# Cooler.net
KiCad netlist of a schematic drawn in EAGLE
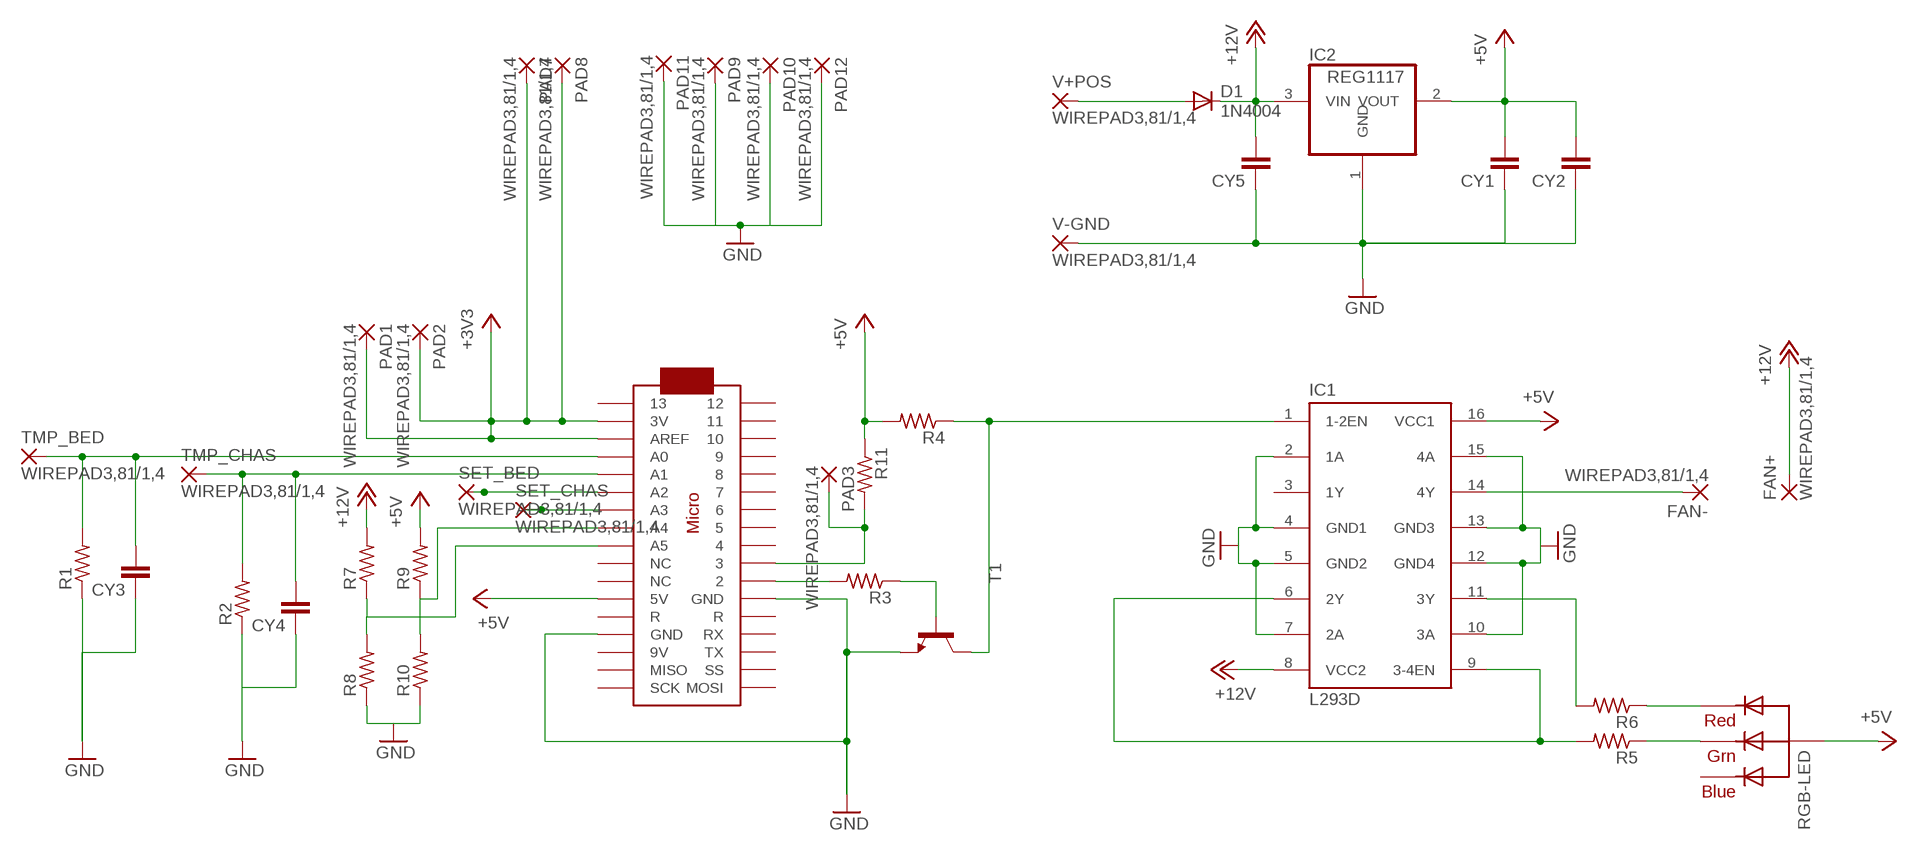
[diagram p0: schematic, sheet 1]

(export (version "E")
  (design (tool "Eeschema 10.0.6"))
  (components
    (comp (ref "CY1")
      (value "CYYC7B5")
      (footprint "eagle-import:YC7B5")
      (libsource (lib "eagle-import") (part "CYYC7B5"))
    )
    (comp (ref "CY2")
      (value "CYYC7B5")
      (footprint "eagle-import:YC7B5")
      (libsource (lib "eagle-import") (part "CYYC7B5"))
    )
    (comp (ref "CY3")
      (value "CYYC7B5")
      (footprint "eagle-import:YC7B5")
      (libsource (lib "eagle-import") (part "CYYC7B5"))
    )
    (comp (ref "CY4")
      (value "CYYC7B5")
      (footprint "eagle-import:YC7B5")
      (libsource (lib "eagle-import") (part "CYYC7B5"))
    )
    (comp (ref "CY5")
      (value "CYYC7B5")
      (footprint "eagle-import:YC7B5")
      (libsource (lib "eagle-import") (part "CYYC7B5"))
    )
    (comp (ref "D1")
      (value "1N4004")
      (footprint "eagle-import:DO41-10")
      (libsource (lib "eagle-import") (part "1N4004"))
    )
    (comp (ref "FAN+")
      (value "WIREPAD3,81/1,4")
      (footprint "eagle-import:3,81_1,4")
      (libsource (lib "eagle-import") (part "WIREPAD3,81/1,4"))
    )
    (comp (ref "FAN-")
      (value "WIREPAD3,81/1,4")
      (footprint "eagle-import:3,81_1,4")
      (libsource (lib "eagle-import") (part "WIREPAD3,81/1,4"))
    )
    (comp (ref "IC1")
      (value "L293D")
      (footprint "eagle-import:DIL16")
      (libsource (lib "eagle-import") (part "L293D"))
    )
    (comp (ref "IC2")
      (value "REG1117")
      (footprint "eagle-import:SOT223")
      (libsource (lib "eagle-import") (part "REG1117"))
    )
    (comp (ref "PAD1")
      (value "WIREPAD3,81/1,4")
      (footprint "eagle-import:3,81_1,4")
      (libsource (lib "eagle-import") (part "WIREPAD3,81/1,4"))
    )
    (comp (ref "PAD2")
      (value "WIREPAD3,81/1,4")
      (footprint "eagle-import:3,81_1,4")
      (libsource (lib "eagle-import") (part "WIREPAD3,81/1,4"))
    )
    (comp (ref "PAD3")
      (value "WIREPAD3,81/1,4")
      (footprint "eagle-import:3,81_1,4")
      (libsource (lib "eagle-import") (part "WIREPAD3,81/1,4"))
    )
    (comp (ref "PAD7")
      (value "WIREPAD3,81/1,4")
      (footprint "eagle-import:3,81_1,4")
      (libsource (lib "eagle-import") (part "WIREPAD3,81/1,4"))
    )
    (comp (ref "PAD8")
      (value "WIREPAD3,81/1,4")
      (footprint "eagle-import:3,81_1,4")
      (libsource (lib "eagle-import") (part "WIREPAD3,81/1,4"))
    )
    (comp (ref "PAD9")
      (value "WIREPAD3,81/1,4")
      (footprint "eagle-import:3,81_1,4")
      (libsource (lib "eagle-import") (part "WIREPAD3,81/1,4"))
    )
    (comp (ref "PAD10")
      (value "WIREPAD3,81/1,4")
      (footprint "eagle-import:3,81_1,4")
      (libsource (lib "eagle-import") (part "WIREPAD3,81/1,4"))
    )
    (comp (ref "PAD11")
      (value "WIREPAD3,81/1,4")
      (footprint "eagle-import:3,81_1,4")
      (libsource (lib "eagle-import") (part "WIREPAD3,81/1,4"))
    )
    (comp (ref "PAD12")
      (value "WIREPAD3,81/1,4")
      (footprint "eagle-import:3,81_1,4")
      (libsource (lib "eagle-import") (part "WIREPAD3,81/1,4"))
    )
    (comp (ref "R1")
      (value "R-US_0309/10")
      (footprint "eagle-import:0309_10")
      (libsource (lib "eagle-import") (part "R-US_0309/10"))
    )
    (comp (ref "R2")
      (value "R-US_0309/10")
      (footprint "eagle-import:0309_10")
      (libsource (lib "eagle-import") (part "R-US_0309/10"))
    )
    (comp (ref "R3")
      (value "R-US_0309/10")
      (footprint "eagle-import:0309_10")
      (libsource (lib "eagle-import") (part "R-US_0309/10"))
    )
    (comp (ref "R4")
      (value "R-US_0309/10")
      (footprint "eagle-import:0309_10")
      (libsource (lib "eagle-import") (part "R-US_0309/10"))
    )
    (comp (ref "R5")
      (value "R-US_0309/12")
      (footprint "eagle-import:0309_12")
      (libsource (lib "eagle-import") (part "R-US_0309/12"))
    )
    (comp (ref "R6")
      (value "R-US_0309/12")
      (footprint "eagle-import:0309_12")
      (libsource (lib "eagle-import") (part "R-US_0309/12"))
    )
    (comp (ref "R7")
      (value "R-US_0309/12")
      (footprint "eagle-import:0309_12")
      (libsource (lib "eagle-import") (part "R-US_0309/12"))
    )
    (comp (ref "R8")
      (value "R-US_0309/10")
      (footprint "eagle-import:0309_10")
      (libsource (lib "eagle-import") (part "R-US_0309/10"))
    )
    (comp (ref "R9")
      (value "R-US_0309/12")
      (footprint "eagle-import:0309_12")
      (libsource (lib "eagle-import") (part "R-US_0309/12"))
    )
    (comp (ref "R10")
      (value "R-US_0309/10")
      (footprint "eagle-import:0309_10")
      (libsource (lib "eagle-import") (part "R-US_0309/10"))
    )
    (comp (ref "R11")
      (value "R-US_0309/10")
      (footprint "eagle-import:0309_10")
      (libsource (lib "eagle-import") (part "R-US_0309/10"))
    )
    (comp (ref "RGB-LED")
      (value "RGBLED_CA-5MM")
      (footprint "eagle-import:LED5MMRGB")
      (libsource (lib "eagle-import") (part "RGBLED_CA-5MM"))
    )
    (comp (ref "SET_BED")
      (value "WIREPAD3,81/1,4")
      (footprint "eagle-import:3,81_1,4")
      (libsource (lib "eagle-import") (part "WIREPAD3,81/1,4"))
    )
    (comp (ref "SET_CHAS")
      (value "WIREPAD3,81/1,4")
      (footprint "eagle-import:3,81_1,4")
      (libsource (lib "eagle-import") (part "WIREPAD3,81/1,4"))
    )
    (comp (ref "T1")
      (value "2N2222-NPN-TO92-EBC")
      (footprint "eagle-import:TO92-EBC")
      (libsource (lib "eagle-import") (part "-NPN-TO92-EBC2N2222"))
    )
    (comp (ref "TMP_BED")
      (value "WIREPAD3,81/1,4")
      (footprint "eagle-import:3,81_1,4")
      (libsource (lib "eagle-import") (part "WIREPAD3,81/1,4"))
    )
    (comp (ref "TMP_CHAS")
      (value "WIREPAD3,81/1,4")
      (footprint "eagle-import:3,81_1,4")
      (libsource (lib "eagle-import") (part "WIREPAD3,81/1,4"))
    )
    (comp (ref "U$1")
      (value "ARDUINOMICRO")
      (footprint "eagle-import:ARDUINOMICRO")
      (libsource (lib "eagle-import") (part "ARDUINOMICRO"))
    )
    (comp (ref "V+POS")
      (value "WIREPAD3,81/1,4")
      (footprint "eagle-import:3,81_1,4")
      (libsource (lib "eagle-import") (part "WIREPAD3,81/1,4"))
    )
    (comp (ref "V-GND")
      (value "WIREPAD3,81/1,4")
      (footprint "eagle-import:3,81_1,4")
      (libsource (lib "eagle-import") (part "WIREPAD3,81/1,4"))
    )
  )
  (nets
    (net (code "1") (name "+3V3") (class "Default")
      (node (ref "PAD1") (pin "1") (pinfunction "P_1") (pintype "passive"))
      (node (ref "PAD2") (pin "1") (pinfunction "P_1") (pintype "passive"))
      (node (ref "PAD7") (pin "1") (pinfunction "P_1") (pintype "passive"))
      (node (ref "PAD8") (pin "1") (pinfunction "P_1") (pintype "passive"))
      (node (ref "U$1") (pin "P$32") (pinfunction "AREF_P$32") (pintype "bidirectional"))
      (node (ref "U$1") (pin "P$33") (pinfunction "3V_P$33") (pintype "bidirectional"))
    )
    (net (code "2") (name "+5V") (class "Default")
      (node (ref "CY1") (pin "2") (pinfunction "2_2") (pintype "passive"))
      (node (ref "CY2") (pin "2") (pinfunction "2_2") (pintype "passive"))
      (node (ref "IC1") (pin "16") (pinfunction "VCC1_16") (pintype "power_in"))
      (node (ref "IC2") (pin "2") (pinfunction "VOUT_2") (pintype "output"))
      (node (ref "R11") (pin "1") (pinfunction "1_1") (pintype "passive"))
      (node (ref "R4") (pin "2") (pinfunction "2_2") (pintype "passive"))
      (node (ref "R9") (pin "2") (pinfunction "2_2") (pintype "passive"))
      (node (ref "RGB-LED") (pin "2") (pinfunction "VCC_2") (pintype "bidirectional"))
      (node (ref "U$1") (pin "P$23") (pinfunction "5V_P$23") (pintype "bidirectional"))
    )
    (net (code "3") (name "+12V") (class "Default")
      (node (ref "CY5") (pin "2") (pinfunction "2_2") (pintype "passive"))
      (node (ref "D1") (pin "C") (pinfunction "C_C") (pintype "passive"))
      (node (ref "FAN+") (pin "1") (pinfunction "P_1") (pintype "passive"))
      (node (ref "IC1") (pin "8") (pinfunction "VCC2_8") (pintype "power_in"))
      (node (ref "IC2") (pin "3") (pinfunction "VIN_3") (pintype "input"))
      (node (ref "R7") (pin "2") (pinfunction "2_2") (pintype "passive"))
    )
    (net (code "4") (name "GND") (class "Default")
      (node (ref "CY1") (pin "1") (pinfunction "1_1") (pintype "passive"))
      (node (ref "CY2") (pin "1") (pinfunction "1_1") (pintype "passive"))
      (node (ref "CY3") (pin "1") (pinfunction "1_1") (pintype "passive"))
      (node (ref "CY4") (pin "1") (pinfunction "1_1") (pintype "passive"))
      (node (ref "CY5") (pin "1") (pinfunction "1_1") (pintype "passive"))
      (node (ref "IC1") (pin "10") (pinfunction "3A_10") (pintype "input"))
      (node (ref "IC1") (pin "12") (pinfunction "GND4_12") (pintype "power_in"))
      (node (ref "IC1") (pin "13") (pinfunction "GND3_13") (pintype "power_in"))
      (node (ref "IC1") (pin "15") (pinfunction "4A_15") (pintype "input"))
      (node (ref "IC1") (pin "2") (pinfunction "1A_2") (pintype "input"))
      (node (ref "IC1") (pin "4") (pinfunction "GND1_4") (pintype "power_in"))
      (node (ref "IC1") (pin "5") (pinfunction "GND2_5") (pintype "power_in"))
      (node (ref "IC1") (pin "7") (pinfunction "2A_7") (pintype "input"))
      (node (ref "IC2") (pin "1") (pinfunction "GND_1") (pintype "power_in"))
      (node (ref "PAD10") (pin "1") (pinfunction "P_1") (pintype "passive"))
      (node (ref "PAD11") (pin "1") (pinfunction "P_1") (pintype "passive"))
      (node (ref "PAD12") (pin "1") (pinfunction "P_1") (pintype "passive"))
      (node (ref "PAD9") (pin "1") (pinfunction "P_1") (pintype "passive"))
      (node (ref "R1") (pin "1") (pinfunction "1_1") (pintype "passive"))
      (node (ref "R10") (pin "1") (pinfunction "1_1") (pintype "passive"))
      (node (ref "R2") (pin "1") (pinfunction "1_1") (pintype "passive"))
      (node (ref "R8") (pin "1") (pinfunction "1_1") (pintype "passive"))
      (node (ref "T1") (pin "E") (pinfunction "E_E") (pintype "passive"))
      (node (ref "U$1") (pin "P$12") (pinfunction "GND_P$12") (pintype "bidirectional"))
      (node (ref "U$1") (pin "P$21") (pinfunction "GND_P$21") (pintype "bidirectional"))
      (node (ref "V-GND") (pin "1") (pinfunction "P_1") (pintype "passive"))
    )
    (net (code "5") (name "Net-(FAN--P)") (class "Default")
      (node (ref "FAN-") (pin "1") (pinfunction "P_1") (pintype "passive"))
      (node (ref "IC1") (pin "14") (pinfunction "4Y_14") (pintype "output"))
    )
    (net (code "6") (name "Net-(IC1-1-2EN)") (class "Default")
      (node (ref "IC1") (pin "1") (pinfunction "1-2EN_1") (pintype "input"))
      (node (ref "R4") (pin "1") (pinfunction "1_1") (pintype "passive"))
      (node (ref "T1") (pin "C") (pinfunction "C_C") (pintype "passive"))
    )
    (net (code "7") (name "Net-(IC1-2Y)") (class "Default")
      (node (ref "IC1") (pin "6") (pinfunction "2Y_6") (pintype "output"))
      (node (ref "IC1") (pin "9") (pinfunction "3-4EN_9") (pintype "input"))
      (node (ref "R5") (pin "2") (pinfunction "2_2") (pintype "passive"))
    )
    (net (code "8") (name "Net-(IC1-3Y)") (class "Default")
      (node (ref "IC1") (pin "11") (pinfunction "3Y_11") (pintype "output"))
      (node (ref "R6") (pin "2") (pinfunction "2_2") (pintype "passive"))
    )
    (net (code "9") (name "Net-(PAD3-P)") (class "Default")
      (node (ref "PAD3") (pin "1") (pinfunction "P_1") (pintype "passive"))
      (node (ref "R11") (pin "2") (pinfunction "2_2") (pintype "passive"))
      (node (ref "U$1") (pin "P$10") (pinfunction "3_P$10") (pintype "bidirectional"))
    )
    (net (code "10") (name "Net-(R3-Pad1)") (class "Default")
      (node (ref "R3") (pin "1") (pinfunction "1_1") (pintype "passive"))
      (node (ref "T1") (pin "B") (pinfunction "B_B") (pintype "passive"))
    )
    (net (code "11") (name "Net-(RGB-LED-GREEN)") (class "Default")
      (node (ref "R5") (pin "1") (pinfunction "1_1") (pintype "passive"))
      (node (ref "RGB-LED") (pin "3") (pinfunction "GREEN_3") (pintype "bidirectional"))
    )
    (net (code "12") (name "Net-(RGB-LED-RED)") (class "Default")
      (node (ref "R6") (pin "1") (pinfunction "1_1") (pintype "passive"))
      (node (ref "RGB-LED") (pin "1") (pinfunction "RED_1") (pintype "bidirectional"))
    )
    (net (code "13") (name "Net-(SET_BED-P)") (class "Default")
      (node (ref "SET_BED") (pin "1") (pinfunction "P_1") (pintype "passive"))
      (node (ref "U$1") (pin "P$29") (pinfunction "A2_P$29") (pintype "bidirectional"))
    )
    (net (code "14") (name "Net-(SET_CHAS-P)") (class "Default")
      (node (ref "SET_CHAS") (pin "1") (pinfunction "P_1") (pintype "passive"))
      (node (ref "U$1") (pin "P$28") (pinfunction "A3_P$28") (pintype "bidirectional"))
    )
    (net (code "15") (name "Net-(TMP_BED-P)") (class "Default")
      (node (ref "CY3") (pin "2") (pinfunction "2_2") (pintype "passive"))
      (node (ref "R1") (pin "2") (pinfunction "2_2") (pintype "passive"))
      (node (ref "TMP_BED") (pin "1") (pinfunction "P_1") (pintype "passive"))
      (node (ref "U$1") (pin "P$31") (pinfunction "A0_P$31") (pintype "bidirectional"))
    )
    (net (code "16") (name "Net-(TMP_CHAS-P)") (class "Default")
      (node (ref "CY4") (pin "2") (pinfunction "2_2") (pintype "passive"))
      (node (ref "R2") (pin "2") (pinfunction "2_2") (pintype "passive"))
      (node (ref "TMP_CHAS") (pin "1") (pinfunction "P_1") (pintype "passive"))
      (node (ref "U$1") (pin "P$30") (pinfunction "A1_P$30") (pintype "bidirectional"))
    )
    (net (code "17") (name "Net-(U$1-2)") (class "Default")
      (node (ref "R3") (pin "2") (pinfunction "2_2") (pintype "passive"))
      (node (ref "U$1") (pin "P$11") (pinfunction "2_P$11") (pintype "bidirectional"))
    )
    (net (code "18") (name "Net-(U$1-A4)") (class "Default")
      (node (ref "R10") (pin "2") (pinfunction "2_2") (pintype "passive"))
      (node (ref "R9") (pin "1") (pinfunction "1_1") (pintype "passive"))
      (node (ref "U$1") (pin "P$27") (pinfunction "A4_P$27") (pintype "bidirectional"))
    )
    (net (code "19") (name "Net-(U$1-A5)") (class "Default")
      (node (ref "R7") (pin "1") (pinfunction "1_1") (pintype "passive"))
      (node (ref "R8") (pin "2") (pinfunction "2_2") (pintype "passive"))
      (node (ref "U$1") (pin "P$26") (pinfunction "A5_P$26") (pintype "bidirectional"))
    )
    (net (code "20") (name "Net-(V+POS-P)") (class "Default")
      (node (ref "D1") (pin "A") (pinfunction "A_A") (pintype "passive"))
      (node (ref "V+POS") (pin "1") (pinfunction "P_1") (pintype "passive"))
    )
    (net (code "21") (name "unconnected-(IC1-1Y-Pad3)") (class "Default")
      (node (ref "IC1") (pin "3") (pinfunction "1Y_3") (pintype "output"))
    )
    (net (code "22") (name "unconnected-(RGB-LED-BLUE-Pad4)") (class "Default")
      (node (ref "RGB-LED") (pin "4") (pinfunction "BLUE_4") (pintype "bidirectional"))
    )
    (net (code "23") (name "unconnected-(U$1-4-PadP$9)") (class "Default")
      (node (ref "U$1") (pin "P$9") (pinfunction "4_P$9") (pintype "bidirectional"))
    )
    (net (code "24") (name "unconnected-(U$1-5-PadP$8)") (class "Default")
      (node (ref "U$1") (pin "P$8") (pinfunction "5_P$8") (pintype "bidirectional"))
    )
    (net (code "25") (name "unconnected-(U$1-6-PadP$7)") (class "Default")
      (node (ref "U$1") (pin "P$7") (pinfunction "6_P$7") (pintype "bidirectional"))
    )
    (net (code "26") (name "unconnected-(U$1-7-PadP$6)") (class "Default")
      (node (ref "U$1") (pin "P$6") (pinfunction "7_P$6") (pintype "bidirectional"))
    )
    (net (code "27") (name "unconnected-(U$1-8-PadP$5)") (class "Default")
      (node (ref "U$1") (pin "P$5") (pinfunction "8_P$5") (pintype "bidirectional"))
    )
    (net (code "28") (name "unconnected-(U$1-9-PadP$4)") (class "Default")
      (node (ref "U$1") (pin "P$4") (pinfunction "9_P$4") (pintype "bidirectional"))
    )
    (net (code "29") (name "unconnected-(U$1-9V-PadP$20)") (class "Default")
      (node (ref "U$1") (pin "P$20") (pinfunction "9V_P$20") (pintype "bidirectional"))
    )
    (net (code "30") (name "unconnected-(U$1-10-PadP$3)") (class "Default")
      (node (ref "U$1") (pin "P$3") (pinfunction "10_P$3") (pintype "bidirectional"))
    )
    (net (code "31") (name "unconnected-(U$1-11-PadP$2)") (class "Default")
      (node (ref "U$1") (pin "P$2") (pinfunction "11_P$2") (pintype "bidirectional"))
    )
    (net (code "32") (name "unconnected-(U$1-12-PadP$1)") (class "Default")
      (node (ref "U$1") (pin "P$1") (pinfunction "12_P$1") (pintype "bidirectional"))
    )
    (net (code "33") (name "unconnected-(U$1-13-PadP$34)") (class "Default")
      (node (ref "U$1") (pin "P$34") (pinfunction "13_P$34") (pintype "bidirectional"))
    )
    (net (code "34") (name "unconnected-(U$1-MISO-PadP$19)") (class "Default")
      (node (ref "U$1") (pin "P$19") (pinfunction "MISO_P$19") (pintype "bidirectional"))
    )
    (net (code "35") (name "unconnected-(U$1-MOSI-PadP$17)") (class "Default")
      (node (ref "U$1") (pin "P$17") (pinfunction "MOSI_P$17") (pintype "bidirectional"))
    )
    (net (code "36") (name "unconnected-(U$1-NC-PadP$24)") (class "Default")
      (node (ref "U$1") (pin "P$24") (pinfunction "NC_P$24") (pintype "bidirectional"))
    )
    (net (code "37") (name "unconnected-(U$1-NC-PadP$25)") (class "Default")
      (node (ref "U$1") (pin "P$25") (pinfunction "NC_P$25") (pintype "bidirectional"))
    )
    (net (code "38") (name "unconnected-(U$1-R-PadP$13)") (class "Default")
      (node (ref "U$1") (pin "P$13") (pinfunction "R_P$13") (pintype "bidirectional"))
    )
    (net (code "39") (name "unconnected-(U$1-R-PadP$22)") (class "Default")
      (node (ref "U$1") (pin "P$22") (pinfunction "R_P$22") (pintype "bidirectional"))
    )
    (net (code "40") (name "unconnected-(U$1-RX-PadP$14)") (class "Default")
      (node (ref "U$1") (pin "P$14") (pinfunction "RX_P$14") (pintype "bidirectional"))
    )
    (net (code "41") (name "unconnected-(U$1-SCK-PadP$18)") (class "Default")
      (node (ref "U$1") (pin "P$18") (pinfunction "SCK_P$18") (pintype "bidirectional"))
    )
    (net (code "42") (name "unconnected-(U$1-SS-PadP$16)") (class "Default")
      (node (ref "U$1") (pin "P$16") (pinfunction "SS_P$16") (pintype "bidirectional"))
    )
    (net (code "43") (name "unconnected-(U$1-TX-PadP$15)") (class "Default")
      (node (ref "U$1") (pin "P$15") (pinfunction "TX_P$15") (pintype "bidirectional"))
    )
  )
)
